# dots.net
KiCad netlist of a schematic drawn in EAGLE
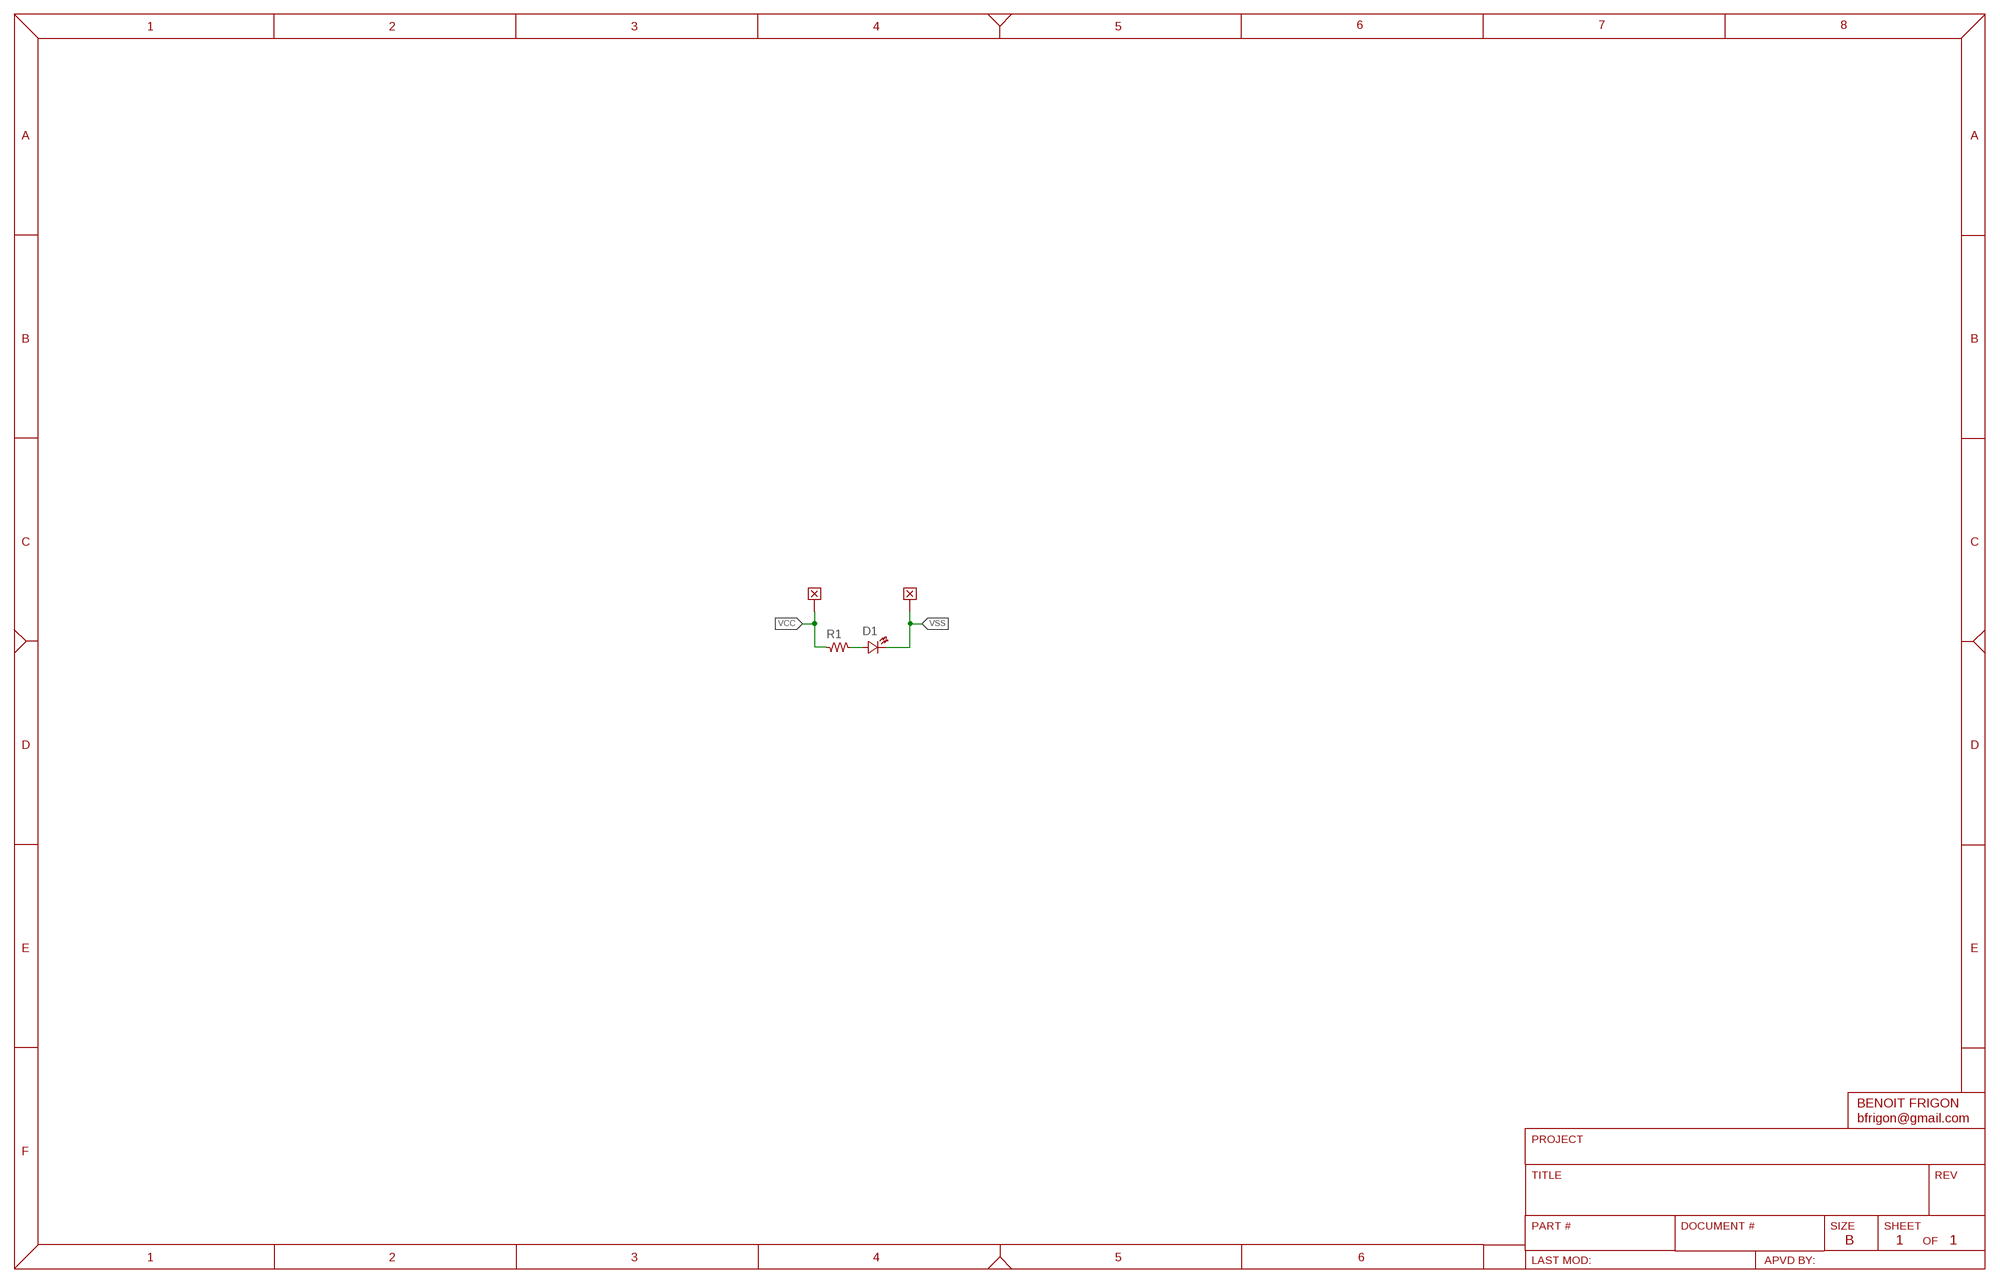
[diagram p0: schematic, sheet 1]

(export (version "E")
  (design (tool "Eeschema 10.0.6"))
  (components
    (comp (ref "D1")
      (value "{ATTR:COLOR}")
      (footprint "eagle-import:CHIPLED_0805")
      (libsource (lib "eagle-import") (part "LED-0805"))
    )
    (comp (ref "R1")
      (value "RES-0603")
      (footprint "eagle-import:SMD_0603")
      (libsource (lib "eagle-import") (part "RES-0603"))
    )
    (comp (ref "W1")
      (value "WIRE")
      (footprint "eagle-import:WIRE_SMT")
      (libsource (lib "eagle-import") (part "WIRE"))
    )
    (comp (ref "W2")
      (value "WIRE")
      (footprint "eagle-import:WIRE_SMT")
      (libsource (lib "eagle-import") (part "WIRE"))
    )
  )
  (nets
    (net (code "1") (name "Net-(D1-PadA)") (class "Default")
      (node (ref "D1") (pin "A") (pinfunction "A_A") (pintype "passive"))
      (node (ref "R1") (pin "2") (pinfunction "2_2") (pintype "passive"))
    )
    (net (code "2") (name "VCC") (class "Default")
      (node (ref "R1") (pin "1") (pinfunction "1_1") (pintype "passive"))
      (node (ref "W1") (pin "1") (pinfunction "P$1_1") (pintype "bidirectional"))
    )
    (net (code "3") (name "VSS") (class "Default")
      (node (ref "D1") (pin "K") (pinfunction "K_K") (pintype "passive"))
      (node (ref "W2") (pin "1") (pinfunction "P$1_1") (pintype "bidirectional"))
    )
  )
)
